# a_civil_hero_vermin_orderv.net
KiCad netlist of a schematic drawn in EAGLE
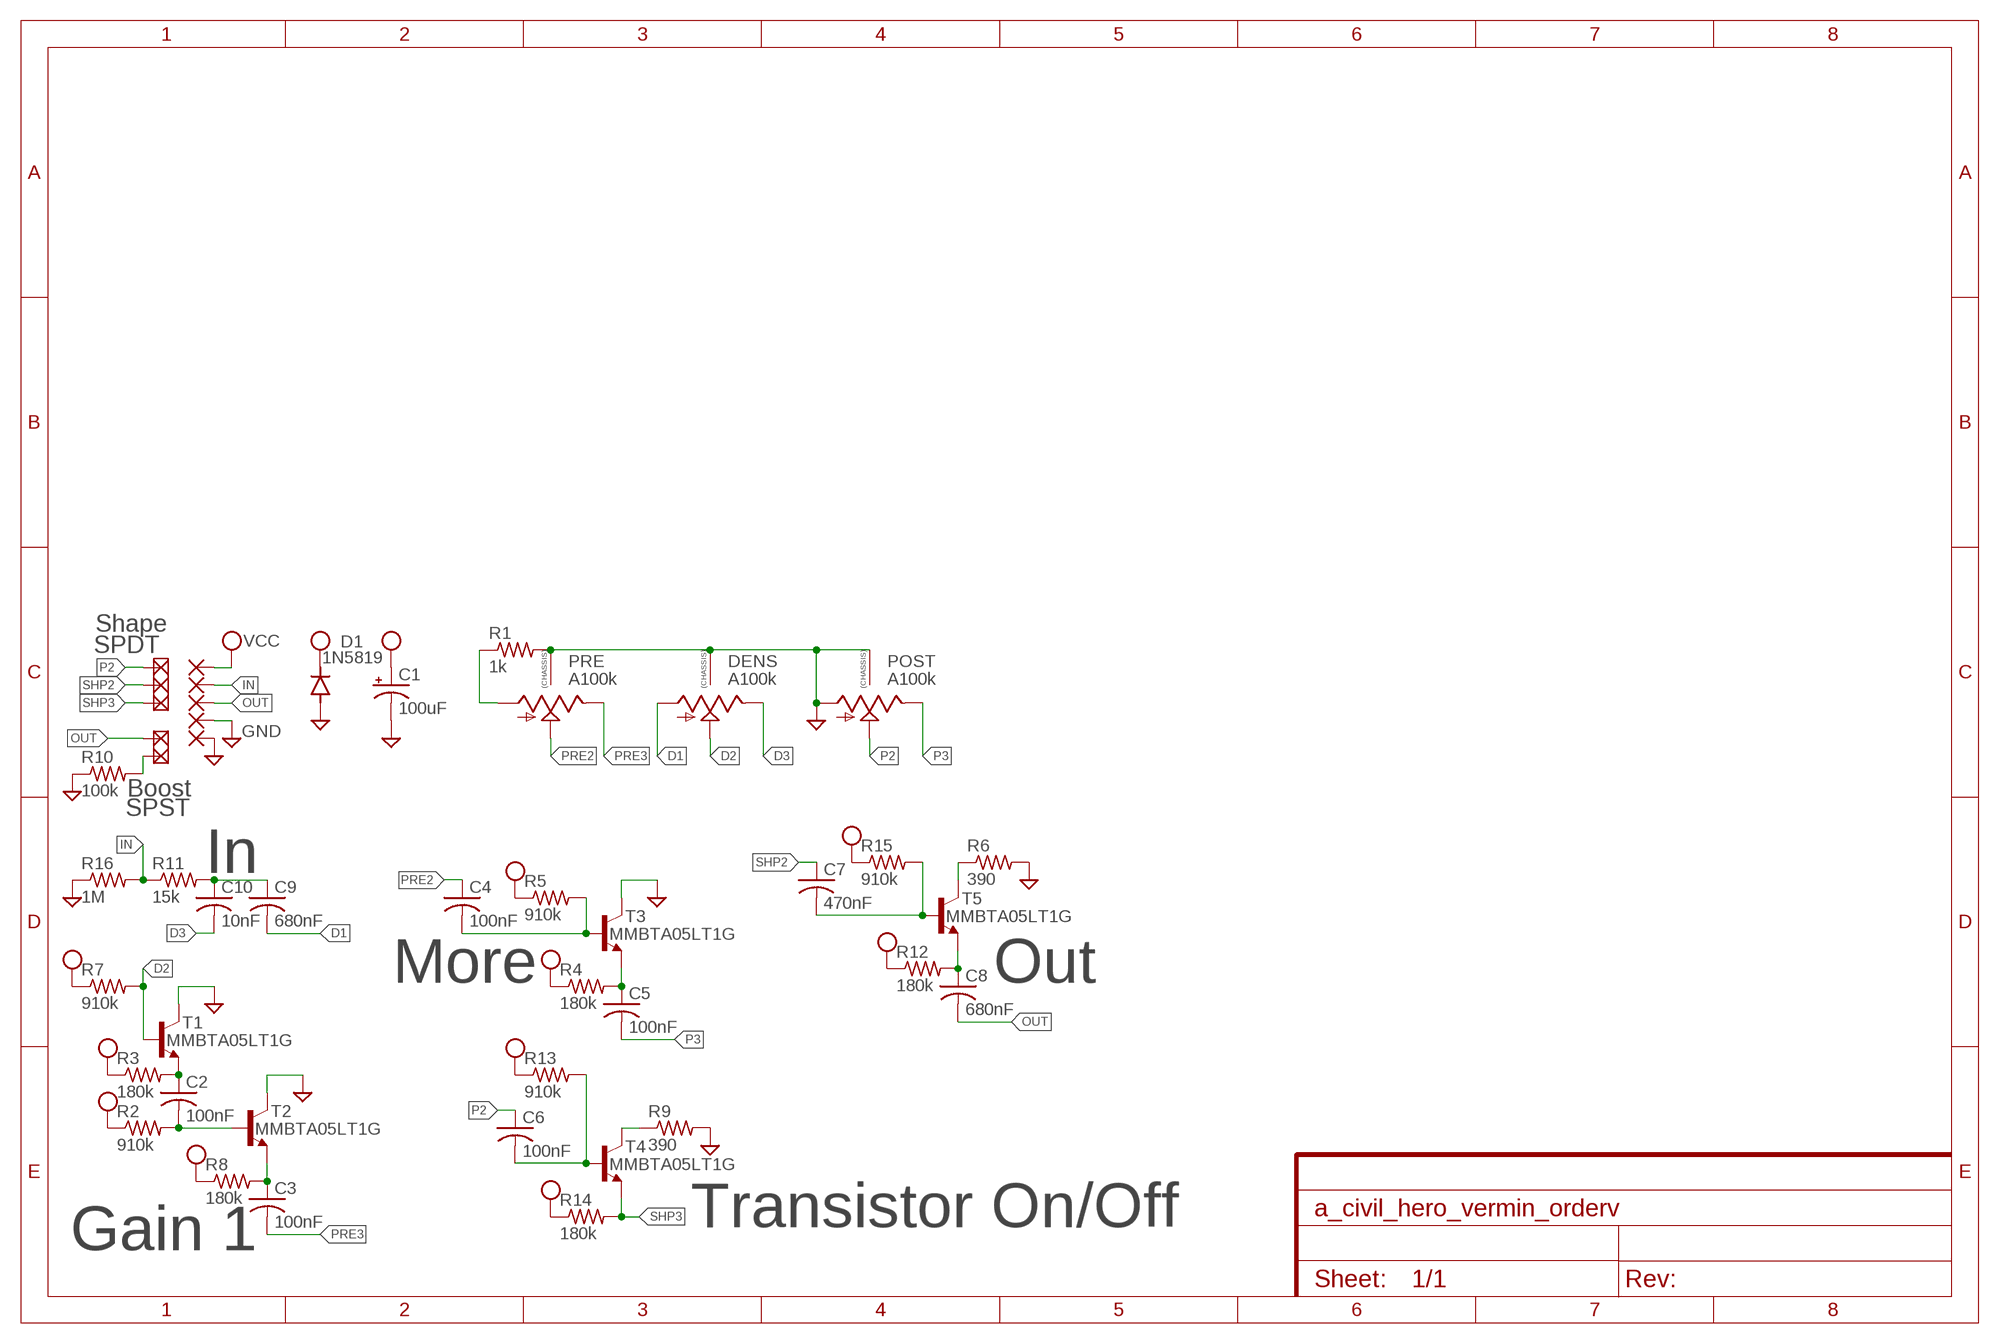
[diagram p0: schematic, sheet 1]

(export (version "E")
  (design (tool "Eeschema 10.0.6"))
  (components
    (comp (ref "BOOST")
      (value "1,6/0,8")
      (footprint "eagle-import:1,6_0,8")
      (libsource (lib "eagle-import") (part "1,6/0,8"))
    )
    (comp (ref "C1")
      (value "100uF")
      (footprint "eagle-import:CPOL-RADIAL-2.5MM-6.5MM")
      (libsource (lib "eagle-import") (part "100UF-POLAR-RADIAL-2.5MM-25V-20%"))
    )
    (comp (ref "C2")
      (value "100nF")
      (footprint "eagle-import:C0603")
      (libsource (lib "eagle-import") (part "C-USC0603"))
    )
    (comp (ref "C3")
      (value "100nF")
      (footprint "eagle-import:C0603")
      (libsource (lib "eagle-import") (part "C-USC0603"))
    )
    (comp (ref "C4")
      (value "100nF")
      (footprint "eagle-import:C0603")
      (libsource (lib "eagle-import") (part "C-USC0603"))
    )
    (comp (ref "C5")
      (value "100nF")
      (footprint "eagle-import:C0603")
      (libsource (lib "eagle-import") (part "C-USC0603"))
    )
    (comp (ref "C6")
      (value "100nF")
      (footprint "eagle-import:C0603")
      (libsource (lib "eagle-import") (part "C-USC0603"))
    )
    (comp (ref "C7")
      (value "470nF")
      (footprint "eagle-import:C0603")
      (libsource (lib "eagle-import") (part "C-USC0603"))
    )
    (comp (ref "C8")
      (value "680nF")
      (footprint "eagle-import:C0603")
      (libsource (lib "eagle-import") (part "C-USC0603"))
    )
    (comp (ref "C9")
      (value "680nF")
      (footprint "eagle-import:C0603")
      (libsource (lib "eagle-import") (part "C-USC0603"))
    )
    (comp (ref "C10")
      (value "10nF")
      (footprint "eagle-import:C0603")
      (libsource (lib "eagle-import") (part "C-USC0603"))
    )
    (comp (ref "D1")
      (value "1N5819")
      (footprint "eagle-import:SOD123")
      (libsource (lib "eagle-import") (part "DIODE-SOD123"))
    )
    (comp (ref "DENS")
      (value "A100k")
      (footprint "eagle-import:9MM_SNAP-IN_POT")
      (libsource (lib "eagle-import") (part "9MM_SNAP-IN_POT_CHASSIS"))
    )
    (comp (ref "PAD1")
      (value "1,6/0,8")
      (footprint "eagle-import:1,6_0,8")
      (libsource (lib "eagle-import") (part "1,6/0,8"))
    )
    (comp (ref "PAD2")
      (value "1,6/0,8")
      (footprint "eagle-import:1,6_0,8")
      (libsource (lib "eagle-import") (part "1,6/0,8"))
    )
    (comp (ref "PAD3")
      (value "1,6/0,8")
      (footprint "eagle-import:1,6_0,8")
      (libsource (lib "eagle-import") (part "1,6/0,8"))
    )
    (comp (ref "PAD4")
      (value "1,6/0,8")
      (footprint "eagle-import:1,6_0,8")
      (libsource (lib "eagle-import") (part "1,6/0,8"))
    )
    (comp (ref "PAD5")
      (value "1,6/0,8")
      (footprint "eagle-import:1,6_0,8")
      (libsource (lib "eagle-import") (part "1,6/0,8"))
    )
    (comp (ref "PAD7")
      (value "1,6/0,8")
      (footprint "eagle-import:1,6_0,8")
      (libsource (lib "eagle-import") (part "1,6/0,8"))
    )
    (comp (ref "POST")
      (value "A100k")
      (footprint "eagle-import:9MM_SNAP-IN_POT")
      (libsource (lib "eagle-import") (part "9MM_SNAP-IN_POT_CHASSIS"))
    )
    (comp (ref "PRE")
      (value "A100k")
      (footprint "eagle-import:9MM_SNAP-IN_POT")
      (libsource (lib "eagle-import") (part "9MM_SNAP-IN_POT_CHASSIS"))
    )
    (comp (ref "R1")
      (value "1k")
      (footprint "eagle-import:R0603")
      (libsource (lib "eagle-import") (part "R-US_R0603"))
    )
    (comp (ref "R2")
      (value "910k")
      (footprint "eagle-import:R0603")
      (libsource (lib "eagle-import") (part "R-US_R0603"))
    )
    (comp (ref "R3")
      (value "180k")
      (footprint "eagle-import:R0603")
      (libsource (lib "eagle-import") (part "R-US_R0603"))
    )
    (comp (ref "R4")
      (value "180k")
      (footprint "eagle-import:R0603")
      (libsource (lib "eagle-import") (part "R-US_R0603"))
    )
    (comp (ref "R5")
      (value "910k")
      (footprint "eagle-import:R0603")
      (libsource (lib "eagle-import") (part "R-US_R0603"))
    )
    (comp (ref "R6")
      (value "390")
      (footprint "eagle-import:R0603")
      (libsource (lib "eagle-import") (part "R-US_R0603"))
    )
    (comp (ref "R7")
      (value "910k")
      (footprint "eagle-import:R0603")
      (libsource (lib "eagle-import") (part "R-US_R0603"))
    )
    (comp (ref "R8")
      (value "180k")
      (footprint "eagle-import:R0603")
      (libsource (lib "eagle-import") (part "R-US_R0603"))
    )
    (comp (ref "R9")
      (value "390")
      (footprint "eagle-import:R0603")
      (libsource (lib "eagle-import") (part "R-US_R0603"))
    )
    (comp (ref "R10")
      (value "100k")
      (footprint "eagle-import:R0603")
      (libsource (lib "eagle-import") (part "R-US_R0603"))
    )
    (comp (ref "R11")
      (value "15k")
      (footprint "eagle-import:R0603")
      (libsource (lib "eagle-import") (part "R-US_R0603"))
    )
    (comp (ref "R12")
      (value "180k")
      (footprint "eagle-import:R0603")
      (libsource (lib "eagle-import") (part "R-US_R0603"))
    )
    (comp (ref "R13")
      (value "910k")
      (footprint "eagle-import:R0603")
      (libsource (lib "eagle-import") (part "R-US_R0603"))
    )
    (comp (ref "R14")
      (value "180k")
      (footprint "eagle-import:R0603")
      (libsource (lib "eagle-import") (part "R-US_R0603"))
    )
    (comp (ref "R15")
      (value "910k")
      (footprint "eagle-import:R0603")
      (libsource (lib "eagle-import") (part "R-US_R0603"))
    )
    (comp (ref "R16")
      (value "1M")
      (footprint "eagle-import:R0603")
      (libsource (lib "eagle-import") (part "R-US_R0603"))
    )
    (comp (ref "SHAPE1")
      (value "1,6/0,8")
      (footprint "eagle-import:1,6_0,8")
      (libsource (lib "eagle-import") (part "1,6/0,8"))
    )
    (comp (ref "SHAPE2")
      (value "1,6/0,8")
      (footprint "eagle-import:1,6_0,8")
      (libsource (lib "eagle-import") (part "1,6/0,8"))
    )
    (comp (ref "SHAPE3")
      (value "1,6/0,8")
      (footprint "eagle-import:1,6_0,8")
      (libsource (lib "eagle-import") (part "1,6/0,8"))
    )
    (comp (ref "T1")
      (value "MMBTA05LT1G")
      (footprint "eagle-import:SOT23-BEC")
      (libsource (lib "eagle-import") (part "-NPN-SOT23-BECMMBTA42LT1"))
    )
    (comp (ref "T2")
      (value "MMBTA05LT1G")
      (footprint "eagle-import:SOT23-BEC")
      (libsource (lib "eagle-import") (part "-NPN-SOT23-BECMMBTA42LT1"))
    )
    (comp (ref "T3")
      (value "MMBTA05LT1G")
      (footprint "eagle-import:SOT23-BEC")
      (libsource (lib "eagle-import") (part "-NPN-SOT23-BECMMBTA42LT1"))
    )
    (comp (ref "T4")
      (value "MMBTA05LT1G")
      (footprint "eagle-import:SOT23-BEC")
      (libsource (lib "eagle-import") (part "-NPN-SOT23-BECMMBTA42LT1"))
    )
    (comp (ref "T5")
      (value "MMBTA05LT1G")
      (footprint "eagle-import:SOT23-BEC")
      (libsource (lib "eagle-import") (part "-NPN-SOT23-BECMMBTA42LT1"))
    )
  )
  (nets
    (net (code "1") (name "D1") (class "Default")
      (node (ref "C9") (pin "2") (pinfunction "2_2") (pintype "passive"))
      (node (ref "DENS") (pin "1") (pinfunction "A_1") (pintype "passive"))
    )
    (net (code "2") (name "D2") (class "Default")
      (node (ref "DENS") (pin "2") (pinfunction "S_2") (pintype "passive"))
      (node (ref "R7") (pin "2") (pinfunction "2_2") (pintype "passive"))
      (node (ref "T1") (pin "B") (pinfunction "B_B") (pintype "passive"))
    )
    (net (code "3") (name "D3") (class "Default")
      (node (ref "C10") (pin "2") (pinfunction "2_2") (pintype "passive"))
      (node (ref "DENS") (pin "3") (pinfunction "E_3") (pintype "passive"))
    )
    (net (code "4") (name "GND") (class "Default")
      (node (ref "C1") (pin "2") (pinfunction "-_2") (pintype "passive"))
      (node (ref "D1") (pin "A") (pinfunction "A_A") (pintype "passive"))
      (node (ref "DENS") (pin "CHASSIS1") (pinfunction "P$1_CHASSIS1") (pintype "passive"))
      (node (ref "DENS") (pin "CHASSIS2") (pinfunction "P$1_CHASSIS2") (pintype "passive"))
      (node (ref "PAD4") (pin "1") (pinfunction "P_1") (pintype "passive"))
      (node (ref "PAD7") (pin "1") (pinfunction "P_1") (pintype "passive"))
      (node (ref "POST") (pin "1") (pinfunction "A_1") (pintype "passive"))
      (node (ref "POST") (pin "CHASSIS1") (pinfunction "P$1_CHASSIS1") (pintype "passive"))
      (node (ref "POST") (pin "CHASSIS2") (pinfunction "P$1_CHASSIS2") (pintype "passive"))
      (node (ref "PRE") (pin "CHASSIS1") (pinfunction "P$1_CHASSIS1") (pintype "passive"))
      (node (ref "PRE") (pin "CHASSIS2") (pinfunction "P$1_CHASSIS2") (pintype "passive"))
      (node (ref "R1") (pin "2") (pinfunction "2_2") (pintype "passive"))
      (node (ref "R10") (pin "1") (pinfunction "1_1") (pintype "passive"))
      (node (ref "R16") (pin "1") (pinfunction "1_1") (pintype "passive"))
      (node (ref "R6") (pin "2") (pinfunction "2_2") (pintype "passive"))
      (node (ref "R9") (pin "2") (pinfunction "2_2") (pintype "passive"))
      (node (ref "T1") (pin "C") (pinfunction "C_C") (pintype "passive"))
      (node (ref "T2") (pin "C") (pinfunction "C_C") (pintype "passive"))
      (node (ref "T3") (pin "C") (pinfunction "C_C") (pintype "passive"))
    )
    (net (code "5") (name "IN") (class "Default")
      (node (ref "PAD2") (pin "1") (pinfunction "P_1") (pintype "passive"))
      (node (ref "R11") (pin "1") (pinfunction "1_1") (pintype "passive"))
      (node (ref "R16") (pin "2") (pinfunction "2_2") (pintype "passive"))
    )
    (net (code "6") (name "Net-(BOOST-P)") (class "Default")
      (node (ref "BOOST") (pin "1") (pinfunction "P_1") (pintype "passive"))
      (node (ref "R10") (pin "2") (pinfunction "2_2") (pintype "passive"))
    )
    (net (code "7") (name "Net-(C2-Pad1)") (class "Default")
      (node (ref "C2") (pin "1") (pinfunction "1_1") (pintype "passive"))
      (node (ref "R3") (pin "2") (pinfunction "2_2") (pintype "passive"))
      (node (ref "T1") (pin "E") (pinfunction "E_E") (pintype "passive"))
    )
    (net (code "8") (name "Net-(C2-Pad2)") (class "Default")
      (node (ref "C2") (pin "2") (pinfunction "2_2") (pintype "passive"))
      (node (ref "R2") (pin "2") (pinfunction "2_2") (pintype "passive"))
      (node (ref "T2") (pin "B") (pinfunction "B_B") (pintype "passive"))
    )
    (net (code "9") (name "Net-(C3-Pad1)") (class "Default")
      (node (ref "C3") (pin "1") (pinfunction "1_1") (pintype "passive"))
      (node (ref "R8") (pin "2") (pinfunction "2_2") (pintype "passive"))
      (node (ref "T2") (pin "E") (pinfunction "E_E") (pintype "passive"))
    )
    (net (code "10") (name "Net-(C4-Pad2)") (class "Default")
      (node (ref "C4") (pin "2") (pinfunction "2_2") (pintype "passive"))
      (node (ref "R5") (pin "2") (pinfunction "2_2") (pintype "passive"))
      (node (ref "T3") (pin "B") (pinfunction "B_B") (pintype "passive"))
    )
    (net (code "11") (name "Net-(C5-Pad1)") (class "Default")
      (node (ref "C5") (pin "1") (pinfunction "1_1") (pintype "passive"))
      (node (ref "R4") (pin "2") (pinfunction "2_2") (pintype "passive"))
      (node (ref "T3") (pin "E") (pinfunction "E_E") (pintype "passive"))
    )
    (net (code "12") (name "Net-(C6-Pad2)") (class "Default")
      (node (ref "C6") (pin "2") (pinfunction "2_2") (pintype "passive"))
      (node (ref "R13") (pin "2") (pinfunction "2_2") (pintype "passive"))
      (node (ref "T4") (pin "B") (pinfunction "B_B") (pintype "passive"))
    )
    (net (code "13") (name "Net-(C7-Pad2)") (class "Default")
      (node (ref "C7") (pin "2") (pinfunction "2_2") (pintype "passive"))
      (node (ref "R15") (pin "2") (pinfunction "2_2") (pintype "passive"))
      (node (ref "T5") (pin "B") (pinfunction "B_B") (pintype "passive"))
    )
    (net (code "14") (name "Net-(C8-Pad1)") (class "Default")
      (node (ref "C8") (pin "1") (pinfunction "1_1") (pintype "passive"))
      (node (ref "R12") (pin "2") (pinfunction "2_2") (pintype "passive"))
      (node (ref "T5") (pin "E") (pinfunction "E_E") (pintype "passive"))
    )
    (net (code "15") (name "Net-(C10-Pad1)") (class "Default")
      (node (ref "C10") (pin "1") (pinfunction "1_1") (pintype "passive"))
      (node (ref "C9") (pin "1") (pinfunction "1_1") (pintype "passive"))
      (node (ref "R11") (pin "2") (pinfunction "2_2") (pintype "passive"))
    )
    (net (code "16") (name "Net-(PRE-A)") (class "Default")
      (node (ref "PRE") (pin "1") (pinfunction "A_1") (pintype "passive"))
      (node (ref "R1") (pin "1") (pinfunction "1_1") (pintype "passive"))
    )
    (net (code "17") (name "Net-(R6-Pad1)") (class "Default")
      (node (ref "R6") (pin "1") (pinfunction "1_1") (pintype "passive"))
      (node (ref "T5") (pin "C") (pinfunction "C_C") (pintype "passive"))
    )
    (net (code "18") (name "Net-(R9-Pad1)") (class "Default")
      (node (ref "R9") (pin "1") (pinfunction "1_1") (pintype "passive"))
      (node (ref "T4") (pin "C") (pinfunction "C_C") (pintype "passive"))
    )
    (net (code "19") (name "OUT") (class "Default")
      (node (ref "C8") (pin "2") (pinfunction "2_2") (pintype "passive"))
      (node (ref "PAD3") (pin "1") (pinfunction "P_1") (pintype "passive"))
      (node (ref "PAD5") (pin "1") (pinfunction "P_1") (pintype "passive"))
    )
    (net (code "20") (name "P2") (class "Default")
      (node (ref "C6") (pin "1") (pinfunction "1_1") (pintype "passive"))
      (node (ref "POST") (pin "2") (pinfunction "S_2") (pintype "passive"))
      (node (ref "SHAPE1") (pin "1") (pinfunction "P_1") (pintype "passive"))
    )
    (net (code "21") (name "P3") (class "Default")
      (node (ref "C5") (pin "2") (pinfunction "2_2") (pintype "passive"))
      (node (ref "POST") (pin "3") (pinfunction "E_3") (pintype "passive"))
    )
    (net (code "22") (name "PRE2") (class "Default")
      (node (ref "C4") (pin "1") (pinfunction "1_1") (pintype "passive"))
      (node (ref "PRE") (pin "2") (pinfunction "S_2") (pintype "passive"))
    )
    (net (code "23") (name "PRE3") (class "Default")
      (node (ref "C3") (pin "2") (pinfunction "2_2") (pintype "passive"))
      (node (ref "PRE") (pin "3") (pinfunction "E_3") (pintype "passive"))
    )
    (net (code "24") (name "SHP2") (class "Default")
      (node (ref "C7") (pin "1") (pinfunction "1_1") (pintype "passive"))
      (node (ref "SHAPE2") (pin "1") (pinfunction "P_1") (pintype "passive"))
    )
    (net (code "25") (name "SHP3") (class "Default")
      (node (ref "R14") (pin "2") (pinfunction "2_2") (pintype "passive"))
      (node (ref "SHAPE3") (pin "1") (pinfunction "P_1") (pintype "passive"))
      (node (ref "T4") (pin "E") (pinfunction "E_E") (pintype "passive"))
    )
    (net (code "26") (name "VCC") (class "Default")
      (node (ref "C1") (pin "1") (pinfunction "+_1") (pintype "passive"))
      (node (ref "D1") (pin "C") (pinfunction "C_C") (pintype "passive"))
      (node (ref "PAD1") (pin "1") (pinfunction "P_1") (pintype "passive"))
      (node (ref "R12") (pin "1") (pinfunction "1_1") (pintype "passive"))
      (node (ref "R13") (pin "1") (pinfunction "1_1") (pintype "passive"))
      (node (ref "R14") (pin "1") (pinfunction "1_1") (pintype "passive"))
      (node (ref "R15") (pin "1") (pinfunction "1_1") (pintype "passive"))
      (node (ref "R2") (pin "1") (pinfunction "1_1") (pintype "passive"))
      (node (ref "R3") (pin "1") (pinfunction "1_1") (pintype "passive"))
      (node (ref "R4") (pin "1") (pinfunction "1_1") (pintype "passive"))
      (node (ref "R5") (pin "1") (pinfunction "1_1") (pintype "passive"))
      (node (ref "R7") (pin "1") (pinfunction "1_1") (pintype "passive"))
      (node (ref "R8") (pin "1") (pinfunction "1_1") (pintype "passive"))
    )
  )
)
